# Accelerometer_Schematic_Rev1.net
KiCad netlist of a schematic drawn in EAGLE
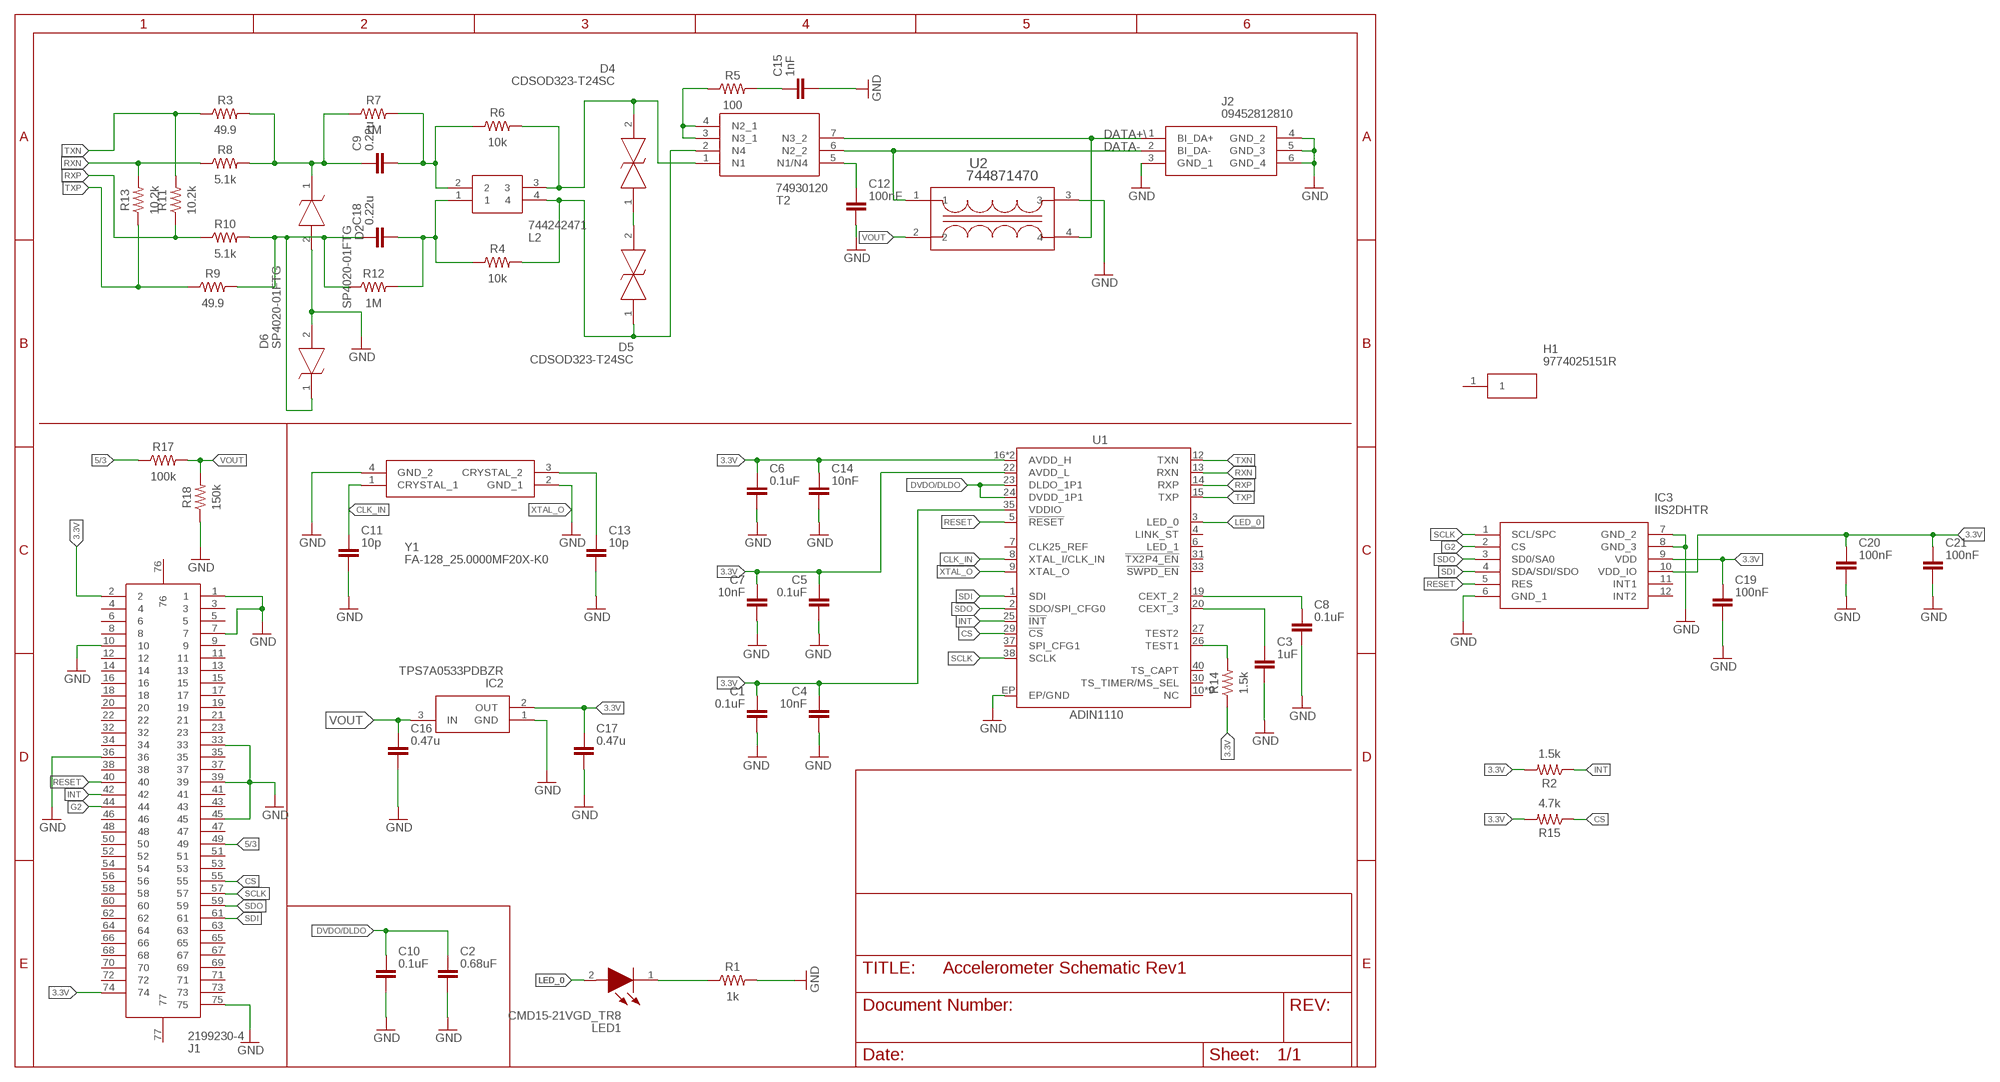
[diagram p0: schematic, sheet 1]

(export (version "E")
  (design (tool "Eeschema 10.0.6"))
  (components
    (comp (ref "C1")
      (value "0.1uF")
      (footprint "eagle-import:CAPC1005X60")
      (libsource (lib "eagle-import") (part "CCHIP-0402(1005-METRIC)_"))
    )
    (comp (ref "C2")
      (value "0.68uF")
      (footprint "eagle-import:CAPC1005X60")
      (libsource (lib "eagle-import") (part "CCHIP-0402(1005-METRIC)_"))
    )
    (comp (ref "C3")
      (value "1uF")
      (footprint "eagle-import:CAPC1005X60")
      (libsource (lib "eagle-import") (part "CCHIP-0402(1005-METRIC)_"))
    )
    (comp (ref "C4")
      (value "10nF")
      (footprint "eagle-import:CAPC1005X60")
      (libsource (lib "eagle-import") (part "CCHIP-0402(1005-METRIC)_"))
    )
    (comp (ref "C5")
      (value "0.1uF")
      (footprint "eagle-import:CAPC1005X60")
      (libsource (lib "eagle-import") (part "CCHIP-0402(1005-METRIC)_"))
    )
    (comp (ref "C6")
      (value "0.1uF")
      (footprint "eagle-import:CAPC1005X60")
      (libsource (lib "eagle-import") (part "CCHIP-0402(1005-METRIC)_"))
    )
    (comp (ref "C7")
      (value "10nF")
      (footprint "eagle-import:CAPC1005X60")
      (libsource (lib "eagle-import") (part "CCHIP-0402(1005-METRIC)_"))
    )
    (comp (ref "C8")
      (value "0.1uF")
      (footprint "eagle-import:CAPC1005X60")
      (libsource (lib "eagle-import") (part "CCHIP-0402(1005-METRIC)_"))
    )
    (comp (ref "C9")
      (value "0.22u")
      (footprint "eagle-import:CAPC1005X60")
      (libsource (lib "eagle-import") (part "CCHIP-0402(1005-METRIC)_"))
    )
    (comp (ref "C10")
      (value "0.1uF")
      (footprint "eagle-import:CAPC1005X60")
      (libsource (lib "eagle-import") (part "CCHIP-0402(1005-METRIC)_"))
    )
    (comp (ref "C11")
      (value "10p")
      (footprint "eagle-import:CAPC1005X60")
      (libsource (lib "eagle-import") (part "CCHIP-0402(1005-METRIC)_"))
    )
    (comp (ref "C12")
      (value "100nF")
      (footprint "eagle-import:CAPC1005X60")
      (libsource (lib "eagle-import") (part "CCHIP-0402(1005-METRIC)_"))
    )
    (comp (ref "C13")
      (value "10p")
      (footprint "eagle-import:CAPC1005X60")
      (libsource (lib "eagle-import") (part "CCHIP-0402(1005-METRIC)_"))
    )
    (comp (ref "C14")
      (value "10nF")
      (footprint "eagle-import:CAPC1005X60")
      (libsource (lib "eagle-import") (part "CCHIP-0402(1005-METRIC)_"))
    )
    (comp (ref "C15")
      (value "1nF")
      (footprint "eagle-import:CAPC1005X60")
      (libsource (lib "eagle-import") (part "CCHIP-0402(1005-METRIC)_"))
    )
    (comp (ref "C16")
      (value "0.47u")
      (footprint "eagle-import:CAPC1005X60")
      (libsource (lib "eagle-import") (part "CCHIP-0402(1005-METRIC)_"))
    )
    (comp (ref "C17")
      (value "0.47u")
      (footprint "eagle-import:CAPC1005X60")
      (libsource (lib "eagle-import") (part "CCHIP-0402(1005-METRIC)_"))
    )
    (comp (ref "C18")
      (value "0.22u")
      (footprint "eagle-import:CAPC1005X60")
      (libsource (lib "eagle-import") (part "CCHIP-0402(1005-METRIC)_"))
    )
    (comp (ref "C19")
      (value "100nF")
      (footprint "eagle-import:CAPC1005X60")
      (libsource (lib "eagle-import") (part "CCHIP-0402(1005-METRIC)_"))
    )
    (comp (ref "C20")
      (value "100nF")
      (footprint "eagle-import:CAPC1005X60")
      (libsource (lib "eagle-import") (part "CCHIP-0402(1005-METRIC)_"))
    )
    (comp (ref "C21")
      (value "100nF")
      (footprint "eagle-import:CAPC1005X60")
      (libsource (lib "eagle-import") (part "CCHIP-0402(1005-METRIC)_"))
    )
    (comp (ref "D2")
      (value "SP4020-01FTG")
      (footprint "eagle-import:SOD2613X114N")
      (fields (field (name "MOUSER_PART_NUMBER") "576-SP4020-01FTG"))
      (libsource (lib "eagle-import") (part "SP4020-01FTG"))
    )
    (comp (ref "D4")
      (value "CDSOD323-T24SC")
      (footprint "eagle-import:SOD2513X114N")
      (fields (field (name "MOUSER_PART_NUMBER") "652-CDSOD323-T24SC"))
      (libsource (lib "eagle-import") (part "CDSOD323-T24SC"))
    )
    (comp (ref "D5")
      (value "CDSOD323-T24SC")
      (footprint "eagle-import:SOD2513X114N")
      (fields (field (name "MOUSER_PART_NUMBER") "652-CDSOD323-T24SC"))
      (libsource (lib "eagle-import") (part "CDSOD323-T24SC"))
    )
    (comp (ref "D6")
      (value "SP4020-01FTG")
      (footprint "eagle-import:SOD2613X114N")
      (fields (field (name "MOUSER_PART_NUMBER") "576-SP4020-01FTG"))
      (libsource (lib "eagle-import") (part "SP4020-01FTG"))
    )
    (comp (ref "H1")
      (value "9774025151R")
      (footprint "eagle-import:9774025151R")
      (fields (field (name "MOUSER_PART_NUMBER") "710-9774025151R"))
      (libsource (lib "eagle-import") (part "9774025151R"))
    )
    (comp (ref "IC2")
      (value "TPS7A0533PDBZR")
      (footprint "eagle-import:SOT95P237X112-3N")
      (fields (field (name "MOUSER_PART_NUMBER") "595-TPS7A0533PDBZR"))
      (libsource (lib "eagle-import") (part "TPS7A0533PDBZR"))
    )
    (comp (ref "IC3")
      (value "IIS2DHTR")
      (footprint "eagle-import:LGA-12")
      (fields (field (name "MOUSER_PART_NUMBER") "511-IIS2DHTR"))
      (libsource (lib "eagle-import") (part "IIS2DHTR"))
    )
    (comp (ref "J1")
      (value "2199230-4")
      (footprint "eagle-import:21992304")
      (fields (field (name "MOUSER_PART_NUMBER") "571-2199230-4"))
      (libsource (lib "eagle-import") (part "2199230-4"))
    )
    (comp (ref "J2")
      (value "09452812810")
      (footprint "eagle-import:09452812810")
      (fields (field (name "MOUSER_PART_NUMBER") "617-09452812810"))
      (libsource (lib "eagle-import") (part "09452812810"))
    )
    (comp (ref "L2")
      (value "744242471")
      (footprint "eagle-import:744242471")
      (fields (field (name "MOUSER_PART_NUMBER") "710-744242471"))
      (libsource (lib "eagle-import") (part "744242471"))
    )
    (comp (ref "LED1")
      (value "CMD15-21VGD_TR8")
      (footprint "eagle-import:LEDC3215X130N")
      (fields
        (field (name "ARROW_PART_NUMBER") "CMD15-21VGD/TR8")
        (field (name "MOUSER_PART_NUMBER") "606-CMD15-21VGD/TR8")
      )
      (libsource (lib "eagle-import") (part "CMD15-21VGD_TR8"))
    )
    (comp (ref "R1")
      (value "1k")
      (footprint "eagle-import:RESC1005X40")
      (libsource (lib "eagle-import") (part "R-USCHIP-0402(1005-METRIC)_"))
    )
    (comp (ref "R2")
      (value "1.5k")
      (footprint "eagle-import:RESC1005X40")
      (libsource (lib "eagle-import") (part "R-USCHIP-0402(1005-METRIC)_"))
    )
    (comp (ref "R3")
      (value "49.9")
      (footprint "eagle-import:RESC1005X40")
      (libsource (lib "eagle-import") (part "R-USCHIP-0402(1005-METRIC)_"))
    )
    (comp (ref "R4")
      (value "10k")
      (footprint "eagle-import:RESC1005X40")
      (libsource (lib "eagle-import") (part "R-USCHIP-0402(1005-METRIC)_"))
    )
    (comp (ref "R5")
      (value "100")
      (footprint "eagle-import:RESC1005X40")
      (libsource (lib "eagle-import") (part "R-USCHIP-0402(1005-METRIC)_"))
    )
    (comp (ref "R6")
      (value "10k")
      (footprint "eagle-import:RESC1005X40")
      (libsource (lib "eagle-import") (part "R-USCHIP-0402(1005-METRIC)_"))
    )
    (comp (ref "R7")
      (value "1M")
      (footprint "eagle-import:RESC1005X40")
      (libsource (lib "eagle-import") (part "R-USCHIP-0402(1005-METRIC)_"))
    )
    (comp (ref "R8")
      (value "5.1k")
      (footprint "eagle-import:RESC1005X40")
      (libsource (lib "eagle-import") (part "R-USCHIP-0402(1005-METRIC)_"))
    )
    (comp (ref "R9")
      (value "49.9")
      (footprint "eagle-import:RESC1005X40")
      (libsource (lib "eagle-import") (part "R-USCHIP-0402(1005-METRIC)_"))
    )
    (comp (ref "R10")
      (value "5.1k")
      (footprint "eagle-import:RESC1005X40")
      (libsource (lib "eagle-import") (part "R-USCHIP-0402(1005-METRIC)_"))
    )
    (comp (ref "R11")
      (value "10.2k")
      (footprint "eagle-import:RESC1005X40")
      (libsource (lib "eagle-import") (part "R-USCHIP-0402(1005-METRIC)_"))
    )
    (comp (ref "R12")
      (value "1M")
      (footprint "eagle-import:RESC1005X40")
      (libsource (lib "eagle-import") (part "R-USCHIP-0402(1005-METRIC)_"))
    )
    (comp (ref "R13")
      (value "10.2k")
      (footprint "eagle-import:RESC1005X40")
      (libsource (lib "eagle-import") (part "R-USCHIP-0402(1005-METRIC)_"))
    )
    (comp (ref "R14")
      (value "1.5k")
      (footprint "eagle-import:RESC1005X40")
      (libsource (lib "eagle-import") (part "R-USCHIP-0402(1005-METRIC)_"))
    )
    (comp (ref "R15")
      (value "4.7k")
      (footprint "eagle-import:RESC1005X40")
      (libsource (lib "eagle-import") (part "R-USCHIP-0402(1005-METRIC)_"))
    )
    (comp (ref "R17")
      (value "100k")
      (footprint "eagle-import:RESC1005X40")
      (libsource (lib "eagle-import") (part "R-USCHIP-0402(1005-METRIC)_"))
    )
    (comp (ref "R18")
      (value "150k")
      (footprint "eagle-import:RESC1005X40")
      (libsource (lib "eagle-import") (part "R-USCHIP-0402(1005-METRIC)_"))
    )
    (comp (ref "T2")
      (value "74930120")
      (footprint "eagle-import:74930120")
      (fields (field (name "MOUSER_PART_NUMBER") "710-74930120"))
      (libsource (lib "eagle-import") (part "74930120"))
    )
    (comp (ref "U1")
      (value "ADIN1110")
      (footprint "eagle-import:LFCSP-40")
      (libsource (lib "eagle-import") (part "ADIN1110"))
    )
    (comp (ref "U2")
      (value "744871470")
      (footprint "eagle-import:SMT_871470_WRE")
      (fields (field (name "COPYRIGHT") "Copyright (C) 2023 Ultra Librarian. All rights reserved."))
      (libsource (lib "eagle-import") (part "744871470"))
    )
    (comp (ref "Y1")
      (value "FA-128_25.0000MF20X-K0")
      (footprint "eagle-import:FA128250000MF20XK0")
      (fields
        (field (name "MANUFACTURER_PART_NUMBER") "FA-128 25.0000MF20X-K0")
        (field (name "MOUSER_PART_NUMBER") "732-FA-12825F20X-K0")
      )
      (libsource (lib "eagle-import") (part "FA-128_25.0000MF20X-K0"))
    )
  )
  (nets
    (net (code "1") (name "/DATA+\\") (class "Default")
      (node (ref "J2") (pin "1") (pinfunction "BI_DA+_1") (pintype "bidirectional"))
      (node (ref "T2") (pin "7") (pinfunction "N3_2_7") (pintype "bidirectional"))
      (node (ref "U2") (pin "4") (pinfunction "4_4") (pintype "passive"))
    )
    (net (code "2") (name "/DATA-") (class "Default")
      (node (ref "J2") (pin "2") (pinfunction "BI_DA-_2") (pintype "bidirectional"))
      (node (ref "T2") (pin "6") (pinfunction "N2_2_6") (pintype "bidirectional"))
      (node (ref "U2") (pin "1") (pinfunction "1_1") (pintype "passive"))
    )
    (net (code "3") (name "3.3V") (class "Default")
      (node (ref "C1") (pin "1") (pinfunction "1_1") (pintype "passive"))
      (node (ref "C14") (pin "1") (pinfunction "1_1") (pintype "passive"))
      (node (ref "C17") (pin "1") (pinfunction "1_1") (pintype "passive"))
      (node (ref "C19") (pin "1") (pinfunction "1_1") (pintype "passive"))
      (node (ref "C20") (pin "1") (pinfunction "1_1") (pintype "passive"))
      (node (ref "C21") (pin "1") (pinfunction "1_1") (pintype "passive"))
      (node (ref "C4") (pin "1") (pinfunction "1_1") (pintype "passive"))
      (node (ref "C5") (pin "1") (pinfunction "1_1") (pintype "passive"))
      (node (ref "C6") (pin "1") (pinfunction "1_1") (pintype "passive"))
      (node (ref "C7") (pin "1") (pinfunction "1_1") (pintype "passive"))
      (node (ref "IC2") (pin "2") (pinfunction "OUT_2") (pintype "output"))
      (node (ref "IC3") (pin "10") (pinfunction "VDD_IO_10") (pintype "bidirectional"))
      (node (ref "IC3") (pin "9") (pinfunction "VDD_9") (pintype "bidirectional"))
      (node (ref "J1") (pin "2") (pinfunction "2_2") (pintype "bidirectional"))
      (node (ref "J1") (pin "74") (pinfunction "74_74") (pintype "bidirectional"))
      (node (ref "R14") (pin "1") (pinfunction "1_1") (pintype "passive"))
      (node (ref "R15") (pin "2") (pinfunction "2_2") (pintype "passive"))
      (node (ref "R2") (pin "2") (pinfunction "2_2") (pintype "passive"))
      (node (ref "U1") (pin "16") (pinfunction "AVDD_H_16") (pintype "bidirectional"))
      (node (ref "U1") (pin "17") (pinfunction "AVDD_H_17") (pintype "bidirectional"))
      (node (ref "U1") (pin "22") (pinfunction "AVDD_L_22") (pintype "bidirectional"))
      (node (ref "U1") (pin "35") (pinfunction "VDDIO_35") (pintype "bidirectional"))
    )
    (net (code "4") (name "5{slash}3") (class "Default")
      (node (ref "J1") (pin "49") (pinfunction "49_49") (pintype "bidirectional"))
      (node (ref "R17") (pin "1") (pinfunction "1_1") (pintype "passive"))
    )
    (net (code "5") (name "CLK_IN") (class "Default")
      (node (ref "C11") (pin "1") (pinfunction "1_1") (pintype "passive"))
      (node (ref "U1") (pin "8") (pinfunction "XTAL_I/CLK_IN_8") (pintype "bidirectional"))
      (node (ref "Y1") (pin "1") (pinfunction "CRYSTAL_1_1") (pintype "bidirectional"))
    )
    (net (code "6") (name "CS") (class "Default")
      (node (ref "J1") (pin "55") (pinfunction "55_55") (pintype "bidirectional"))
      (node (ref "R15") (pin "1") (pinfunction "1_1") (pintype "passive"))
      (node (ref "U1") (pin "29") (pinfunction "~{CS}_29") (pintype "bidirectional"))
    )
    (net (code "7") (name "DVDO{slash}DLDO") (class "Default")
      (node (ref "C10") (pin "1") (pinfunction "1_1") (pintype "passive"))
      (node (ref "C2") (pin "1") (pinfunction "1_1") (pintype "passive"))
      (node (ref "U1") (pin "23") (pinfunction "DLDO_1P1_23") (pintype "bidirectional"))
      (node (ref "U1") (pin "24") (pinfunction "DVDD_1P1_24") (pintype "bidirectional"))
    )
    (net (code "8") (name "G2") (class "Default")
      (node (ref "IC3") (pin "2") (pinfunction "CS_2") (pintype "bidirectional"))
      (node (ref "J1") (pin "44") (pinfunction "44_44") (pintype "bidirectional"))
    )
    (net (code "9") (name "GND") (class "Default")
      (node (ref "C1") (pin "2") (pinfunction "2_2") (pintype "passive"))
      (node (ref "C10") (pin "2") (pinfunction "2_2") (pintype "passive"))
      (node (ref "C11") (pin "2") (pinfunction "2_2") (pintype "passive"))
      (node (ref "C12") (pin "2") (pinfunction "2_2") (pintype "passive"))
      (node (ref "C13") (pin "2") (pinfunction "2_2") (pintype "passive"))
      (node (ref "C14") (pin "2") (pinfunction "2_2") (pintype "passive"))
      (node (ref "C15") (pin "2") (pinfunction "2_2") (pintype "passive"))
      (node (ref "C16") (pin "2") (pinfunction "2_2") (pintype "passive"))
      (node (ref "C17") (pin "2") (pinfunction "2_2") (pintype "passive"))
      (node (ref "C19") (pin "2") (pinfunction "2_2") (pintype "passive"))
      (node (ref "C2") (pin "2") (pinfunction "2_2") (pintype "passive"))
      (node (ref "C20") (pin "2") (pinfunction "2_2") (pintype "passive"))
      (node (ref "C21") (pin "2") (pinfunction "2_2") (pintype "passive"))
      (node (ref "C3") (pin "2") (pinfunction "2_2") (pintype "passive"))
      (node (ref "C4") (pin "2") (pinfunction "2_2") (pintype "passive"))
      (node (ref "C5") (pin "2") (pinfunction "2_2") (pintype "passive"))
      (node (ref "C6") (pin "2") (pinfunction "2_2") (pintype "passive"))
      (node (ref "C7") (pin "2") (pinfunction "2_2") (pintype "passive"))
      (node (ref "C8") (pin "2") (pinfunction "2_2") (pintype "passive"))
      (node (ref "D2") (pin "2") (pinfunction "A_2") (pintype "bidirectional"))
      (node (ref "D6") (pin "2") (pinfunction "A_2") (pintype "bidirectional"))
      (node (ref "IC2") (pin "1") (pinfunction "GND_1") (pintype "power_in"))
      (node (ref "IC3") (pin "6") (pinfunction "GND_1_6") (pintype "bidirectional"))
      (node (ref "IC3") (pin "7") (pinfunction "GND_2_7") (pintype "bidirectional"))
      (node (ref "IC3") (pin "8") (pinfunction "GND_3_8") (pintype "bidirectional"))
      (node (ref "J1") (pin "1") (pinfunction "1_1") (pintype "bidirectional"))
      (node (ref "J1") (pin "10") (pinfunction "10_10") (pintype "bidirectional"))
      (node (ref "J1") (pin "33") (pinfunction "33_33") (pintype "bidirectional"))
      (node (ref "J1") (pin "36") (pinfunction "36_36") (pintype "bidirectional"))
      (node (ref "J1") (pin "39") (pinfunction "39_39") (pintype "bidirectional"))
      (node (ref "J1") (pin "45") (pinfunction "45_45") (pintype "bidirectional"))
      (node (ref "J1") (pin "7") (pinfunction "7_7") (pintype "bidirectional"))
      (node (ref "J1") (pin "75") (pinfunction "75_75") (pintype "bidirectional"))
      (node (ref "J2") (pin "3") (pinfunction "GND_1_3") (pintype "bidirectional"))
      (node (ref "J2") (pin "4") (pinfunction "GND_2_4") (pintype "bidirectional"))
      (node (ref "J2") (pin "5") (pinfunction "GND_3_5") (pintype "bidirectional"))
      (node (ref "J2") (pin "6") (pinfunction "GND_4_6") (pintype "bidirectional"))
      (node (ref "R1") (pin "2") (pinfunction "2_2") (pintype "passive"))
      (node (ref "R18") (pin "1") (pinfunction "1_1") (pintype "passive"))
      (node (ref "U1") (pin "EP") (pinfunction "EP/GND_EP") (pintype "bidirectional"))
      (node (ref "U2") (pin "3") (pinfunction "3_3") (pintype "passive"))
      (node (ref "Y1") (pin "2") (pinfunction "GND_1_2") (pintype "bidirectional"))
      (node (ref "Y1") (pin "4") (pinfunction "GND_2_4") (pintype "bidirectional"))
    )
    (net (code "10") (name "INT") (class "Default")
      (node (ref "J1") (pin "42") (pinfunction "42_42") (pintype "bidirectional"))
      (node (ref "R2") (pin "1") (pinfunction "1_1") (pintype "passive"))
      (node (ref "U1") (pin "25") (pinfunction "~{INT}_25") (pintype "bidirectional"))
    )
    (net (code "11") (name "LED_0") (class "Default")
      (node (ref "LED1") (pin "2") (pinfunction "A_2") (pintype "bidirectional"))
      (node (ref "U1") (pin "3") (pinfunction "LED_0_3") (pintype "bidirectional"))
    )
    (net (code "12") (name "Net-(C9-Pad2)") (class "Default")
      (node (ref "C9") (pin "2") (pinfunction "2_2") (pintype "passive"))
      (node (ref "L2") (pin "2") (pinfunction "2_2") (pintype "bidirectional"))
      (node (ref "R6") (pin "1") (pinfunction "1_1") (pintype "passive"))
      (node (ref "R7") (pin "2") (pinfunction "2_2") (pintype "passive"))
    )
    (net (code "13") (name "Net-(C15-Pad1)") (class "Default")
      (node (ref "C15") (pin "1") (pinfunction "1_1") (pintype "passive"))
      (node (ref "R5") (pin "2") (pinfunction "2_2") (pintype "passive"))
    )
    (net (code "14") (name "Net-(C18-Pad2)") (class "Default")
      (node (ref "C18") (pin "2") (pinfunction "2_2") (pintype "passive"))
      (node (ref "L2") (pin "1") (pinfunction "1_1") (pintype "bidirectional"))
      (node (ref "R12") (pin "2") (pinfunction "2_2") (pintype "passive"))
      (node (ref "R4") (pin "1") (pinfunction "1_1") (pintype "passive"))
    )
    (net (code "15") (name "Net-(D2-K)") (class "Default")
      (node (ref "C9") (pin "1") (pinfunction "1_1") (pintype "passive"))
      (node (ref "D2") (pin "1") (pinfunction "K_1") (pintype "bidirectional"))
      (node (ref "R3") (pin "2") (pinfunction "2_2") (pintype "passive"))
      (node (ref "R7") (pin "1") (pinfunction "1_1") (pintype "passive"))
      (node (ref "R8") (pin "2") (pinfunction "2_2") (pintype "passive"))
    )
    (net (code "16") (name "Net-(D4-Pad1)") (class "Default")
      (node (ref "D4") (pin "1") (pinfunction "1_1") (pintype "bidirectional"))
      (node (ref "D5") (pin "2") (pinfunction "2_2") (pintype "bidirectional"))
    )
    (net (code "17") (name "Net-(D6-K)") (class "Default")
      (node (ref "C18") (pin "1") (pinfunction "1_1") (pintype "passive"))
      (node (ref "D6") (pin "1") (pinfunction "K_1") (pintype "bidirectional"))
      (node (ref "R10") (pin "2") (pinfunction "2_2") (pintype "passive"))
      (node (ref "R12") (pin "1") (pinfunction "1_1") (pintype "passive"))
      (node (ref "R9") (pin "2") (pinfunction "2_2") (pintype "passive"))
    )
    (net (code "18") (name "Net-(LED1-K)") (class "Default")
      (node (ref "LED1") (pin "1") (pinfunction "K_1") (pintype "bidirectional"))
      (node (ref "R1") (pin "1") (pinfunction "1_1") (pintype "passive"))
    )
    (net (code "19") (name "Net-(T2-N1)") (class "Default")
      (node (ref "D4") (pin "2") (pinfunction "2_2") (pintype "bidirectional"))
      (node (ref "L2") (pin "3") (pinfunction "3_3") (pintype "bidirectional"))
      (node (ref "R6") (pin "2") (pinfunction "2_2") (pintype "passive"))
      (node (ref "T2") (pin "1") (pinfunction "N1_1") (pintype "bidirectional"))
    )
    (net (code "20") (name "Net-(T2-N1{slash}N4)") (class "Default")
      (node (ref "C12") (pin "1") (pinfunction "1_1") (pintype "passive"))
      (node (ref "T2") (pin "5") (pinfunction "N1/N4_5") (pintype "bidirectional"))
    )
    (net (code "21") (name "Net-(T2-N2_1)") (class "Default")
      (node (ref "R5") (pin "1") (pinfunction "1_1") (pintype "passive"))
      (node (ref "T2") (pin "3") (pinfunction "N3_1_3") (pintype "bidirectional"))
      (node (ref "T2") (pin "4") (pinfunction "N2_1_4") (pintype "bidirectional"))
    )
    (net (code "22") (name "Net-(T2-N4)") (class "Default")
      (node (ref "D5") (pin "1") (pinfunction "1_1") (pintype "bidirectional"))
      (node (ref "L2") (pin "4") (pinfunction "4_4") (pintype "bidirectional"))
      (node (ref "R4") (pin "2") (pinfunction "2_2") (pintype "passive"))
      (node (ref "T2") (pin "2") (pinfunction "N4_2") (pintype "bidirectional"))
    )
    (net (code "23") (name "Net-(U1-CEXT_2)") (class "Default")
      (node (ref "C8") (pin "1") (pinfunction "1_1") (pintype "passive"))
      (node (ref "U1") (pin "19") (pinfunction "CEXT_2_19") (pintype "bidirectional"))
    )
    (net (code "24") (name "Net-(U1-CEXT_3)") (class "Default")
      (node (ref "C3") (pin "1") (pinfunction "1_1") (pintype "passive"))
      (node (ref "U1") (pin "20") (pinfunction "CEXT_3_20") (pintype "bidirectional"))
    )
    (net (code "25") (name "Net-(U1-TEST1)") (class "Default")
      (node (ref "R14") (pin "2") (pinfunction "2_2") (pintype "passive"))
      (node (ref "U1") (pin "26") (pinfunction "TEST1_26") (pintype "bidirectional"))
    )
    (net (code "26") (name "RESET") (class "Default")
      (node (ref "IC3") (pin "5") (pinfunction "RES_5") (pintype "bidirectional"))
      (node (ref "J1") (pin "40") (pinfunction "40_40") (pintype "bidirectional"))
      (node (ref "U1") (pin "5") (pinfunction "~{RESET}_5") (pintype "bidirectional"))
    )
    (net (code "27") (name "RXN") (class "Default")
      (node (ref "R13") (pin "2") (pinfunction "2_2") (pintype "passive"))
      (node (ref "R8") (pin "1") (pinfunction "1_1") (pintype "passive"))
      (node (ref "U1") (pin "13") (pinfunction "RXN_13") (pintype "bidirectional"))
    )
    (net (code "28") (name "RXP") (class "Default")
      (node (ref "R10") (pin "1") (pinfunction "1_1") (pintype "passive"))
      (node (ref "R11") (pin "1") (pinfunction "1_1") (pintype "passive"))
      (node (ref "U1") (pin "14") (pinfunction "RXP_14") (pintype "bidirectional"))
    )
    (net (code "29") (name "SCLK") (class "Default")
      (node (ref "IC3") (pin "1") (pinfunction "SCL/SPC_1") (pintype "bidirectional"))
      (node (ref "J1") (pin "57") (pinfunction "57_57") (pintype "bidirectional"))
      (node (ref "U1") (pin "38") (pinfunction "SCLK_38") (pintype "bidirectional"))
    )
    (net (code "30") (name "SDI") (class "Default")
      (node (ref "IC3") (pin "4") (pinfunction "SDA/SDI/SDO_4") (pintype "bidirectional"))
      (node (ref "J1") (pin "61") (pinfunction "61_61") (pintype "bidirectional"))
      (node (ref "U1") (pin "1") (pinfunction "SDI_1") (pintype "bidirectional"))
    )
    (net (code "31") (name "SDO") (class "Default")
      (node (ref "IC3") (pin "3") (pinfunction "SD0/SA0_3") (pintype "bidirectional"))
      (node (ref "J1") (pin "59") (pinfunction "59_59") (pintype "bidirectional"))
      (node (ref "U1") (pin "2") (pinfunction "SDO/SPI_CFG0_2") (pintype "bidirectional"))
    )
    (net (code "32") (name "TXN") (class "Default")
      (node (ref "R11") (pin "2") (pinfunction "2_2") (pintype "passive"))
      (node (ref "R3") (pin "1") (pinfunction "1_1") (pintype "passive"))
      (node (ref "U1") (pin "12") (pinfunction "TXN_12") (pintype "bidirectional"))
    )
    (net (code "33") (name "TXP") (class "Default")
      (node (ref "R13") (pin "1") (pinfunction "1_1") (pintype "passive"))
      (node (ref "R9") (pin "1") (pinfunction "1_1") (pintype "passive"))
      (node (ref "U1") (pin "15") (pinfunction "TXP_15") (pintype "bidirectional"))
    )
    (net (code "34") (name "VOUT") (class "Default")
      (node (ref "C16") (pin "1") (pinfunction "1_1") (pintype "passive"))
      (node (ref "IC2") (pin "3") (pinfunction "IN_3") (pintype "input"))
      (node (ref "R17") (pin "2") (pinfunction "2_2") (pintype "passive"))
      (node (ref "R18") (pin "2") (pinfunction "2_2") (pintype "passive"))
      (node (ref "U2") (pin "2") (pinfunction "2_2") (pintype "passive"))
    )
    (net (code "35") (name "XTAL_O") (class "Default")
      (node (ref "C13") (pin "1") (pinfunction "1_1") (pintype "passive"))
      (node (ref "U1") (pin "9") (pinfunction "XTAL_O_9") (pintype "bidirectional"))
      (node (ref "Y1") (pin "3") (pinfunction "CRYSTAL_2_3") (pintype "bidirectional"))
    )
    (net (code "36") (name "unconnected-(H1-Pad1)") (class "Default")
      (node (ref "H1") (pin "1") (pinfunction "1_1") (pintype "bidirectional"))
    )
    (net (code "37") (name "unconnected-(IC3-INT1-Pad11)") (class "Default")
      (node (ref "IC3") (pin "11") (pinfunction "INT1_11") (pintype "bidirectional"))
    )
    (net (code "38") (name "unconnected-(IC3-INT2-Pad12)") (class "Default")
      (node (ref "IC3") (pin "12") (pinfunction "INT2_12") (pintype "bidirectional"))
    )
    (net (code "39") (name "unconnected-(J1-Pad3)") (class "Default")
      (node (ref "J1") (pin "3") (pinfunction "3_3") (pintype "bidirectional"))
    )
    (net (code "40") (name "unconnected-(J1-Pad4)") (class "Default")
      (node (ref "J1") (pin "4") (pinfunction "4_4") (pintype "bidirectional"))
    )
    (net (code "41") (name "unconnected-(J1-Pad5)") (class "Default")
      (node (ref "J1") (pin "5") (pinfunction "5_5") (pintype "bidirectional"))
    )
    (net (code "42") (name "unconnected-(J1-Pad6)") (class "Default")
      (node (ref "J1") (pin "6") (pinfunction "6_6") (pintype "bidirectional"))
    )
    (net (code "43") (name "unconnected-(J1-Pad8)") (class "Default")
      (node (ref "J1") (pin "8") (pinfunction "8_8") (pintype "bidirectional"))
    )
    (net (code "44") (name "unconnected-(J1-Pad9)") (class "Default")
      (node (ref "J1") (pin "9") (pinfunction "9_9") (pintype "bidirectional"))
    )
    (net (code "45") (name "unconnected-(J1-Pad11)") (class "Default")
      (node (ref "J1") (pin "11") (pinfunction "11_11") (pintype "bidirectional"))
    )
    (net (code "46") (name "unconnected-(J1-Pad12)") (class "Default")
      (node (ref "J1") (pin "12") (pinfunction "12_12") (pintype "bidirectional"))
    )
    (net (code "47") (name "unconnected-(J1-Pad13)") (class "Default")
      (node (ref "J1") (pin "13") (pinfunction "13_13") (pintype "bidirectional"))
    )
    (net (code "48") (name "unconnected-(J1-Pad14)") (class "Default")
      (node (ref "J1") (pin "14") (pinfunction "14_14") (pintype "bidirectional"))
    )
    (net (code "49") (name "unconnected-(J1-Pad15)") (class "Default")
      (node (ref "J1") (pin "15") (pinfunction "15_15") (pintype "bidirectional"))
    )
    (net (code "50") (name "unconnected-(J1-Pad16)") (class "Default")
      (node (ref "J1") (pin "16") (pinfunction "16_16") (pintype "bidirectional"))
    )
    (net (code "51") (name "unconnected-(J1-Pad17)") (class "Default")
      (node (ref "J1") (pin "17") (pinfunction "17_17") (pintype "bidirectional"))
    )
    (net (code "52") (name "unconnected-(J1-Pad18)") (class "Default")
      (node (ref "J1") (pin "18") (pinfunction "18_18") (pintype "bidirectional"))
    )
    (net (code "53") (name "unconnected-(J1-Pad19)") (class "Default")
      (node (ref "J1") (pin "19") (pinfunction "19_19") (pintype "bidirectional"))
    )
    (net (code "54") (name "unconnected-(J1-Pad20)") (class "Default")
      (node (ref "J1") (pin "20") (pinfunction "20_20") (pintype "bidirectional"))
    )
    (net (code "55") (name "unconnected-(J1-Pad21)") (class "Default")
      (node (ref "J1") (pin "21") (pinfunction "21_21") (pintype "bidirectional"))
    )
    (net (code "56") (name "unconnected-(J1-Pad22)") (class "Default")
      (node (ref "J1") (pin "22") (pinfunction "22_22") (pintype "bidirectional"))
    )
    (net (code "57") (name "unconnected-(J1-Pad23)") (class "Default")
      (node (ref "J1") (pin "23") (pinfunction "23_23") (pintype "bidirectional"))
    )
    (net (code "58") (name "unconnected-(J1-Pad32)") (class "Default")
      (node (ref "J1") (pin "32") (pinfunction "32_32") (pintype "bidirectional"))
    )
    (net (code "59") (name "unconnected-(J1-Pad34)") (class "Default")
      (node (ref "J1") (pin "34") (pinfunction "34_34") (pintype "bidirectional"))
    )
    (net (code "60") (name "unconnected-(J1-Pad35)") (class "Default")
      (node (ref "J1") (pin "35") (pinfunction "35_35") (pintype "bidirectional"))
    )
    (net (code "61") (name "unconnected-(J1-Pad37)") (class "Default")
      (node (ref "J1") (pin "37") (pinfunction "37_37") (pintype "bidirectional"))
    )
    (net (code "62") (name "unconnected-(J1-Pad38)") (class "Default")
      (node (ref "J1") (pin "38") (pinfunction "38_38") (pintype "bidirectional"))
    )
    (net (code "63") (name "unconnected-(J1-Pad41)") (class "Default")
      (node (ref "J1") (pin "41") (pinfunction "41_41") (pintype "bidirectional"))
    )
    (net (code "64") (name "unconnected-(J1-Pad43)") (class "Default")
      (node (ref "J1") (pin "43") (pinfunction "43_43") (pintype "bidirectional"))
    )
    (net (code "65") (name "unconnected-(J1-Pad46)") (class "Default")
      (node (ref "J1") (pin "46") (pinfunction "46_46") (pintype "bidirectional"))
    )
    (net (code "66") (name "unconnected-(J1-Pad47)") (class "Default")
      (node (ref "J1") (pin "47") (pinfunction "47_47") (pintype "bidirectional"))
    )
    (net (code "67") (name "unconnected-(J1-Pad48)") (class "Default")
      (node (ref "J1") (pin "48") (pinfunction "48_48") (pintype "bidirectional"))
    )
    (net (code "68") (name "unconnected-(J1-Pad50)") (class "Default")
      (node (ref "J1") (pin "50") (pinfunction "50_50") (pintype "bidirectional"))
    )
    (net (code "69") (name "unconnected-(J1-Pad51)") (class "Default")
      (node (ref "J1") (pin "51") (pinfunction "51_51") (pintype "bidirectional"))
    )
    (net (code "70") (name "unconnected-(J1-Pad52)") (class "Default")
      (node (ref "J1") (pin "52") (pinfunction "52_52") (pintype "bidirectional"))
    )
    (net (code "71") (name "unconnected-(J1-Pad53)") (class "Default")
      (node (ref "J1") (pin "53") (pinfunction "53_53") (pintype "bidirectional"))
    )
    (net (code "72") (name "unconnected-(J1-Pad54)") (class "Default")
      (node (ref "J1") (pin "54") (pinfunction "54_54") (pintype "bidirectional"))
    )
    (net (code "73") (name "unconnected-(J1-Pad56)") (class "Default")
      (node (ref "J1") (pin "56") (pinfunction "56_56") (pintype "bidirectional"))
    )
    (net (code "74") (name "unconnected-(J1-Pad58)") (class "Default")
      (node (ref "J1") (pin "58") (pinfunction "58_58") (pintype "bidirectional"))
    )
    (net (code "75") (name "unconnected-(J1-Pad60)") (class "Default")
      (node (ref "J1") (pin "60") (pinfunction "60_60") (pintype "bidirectional"))
    )
    (net (code "76") (name "unconnected-(J1-Pad62)") (class "Default")
      (node (ref "J1") (pin "62") (pinfunction "62_62") (pintype "bidirectional"))
    )
    (net (code "77") (name "unconnected-(J1-Pad63)") (class "Default")
      (node (ref "J1") (pin "63") (pinfunction "63_63") (pintype "bidirectional"))
    )
    (net (code "78") (name "unconnected-(J1-Pad64)") (class "Default")
      (node (ref "J1") (pin "64") (pinfunction "64_64") (pintype "bidirectional"))
    )
    (net (code "79") (name "unconnected-(J1-Pad65)") (class "Default")
      (node (ref "J1") (pin "65") (pinfunction "65_65") (pintype "bidirectional"))
    )
    (net (code "80") (name "unconnected-(J1-Pad66)") (class "Default")
      (node (ref "J1") (pin "66") (pinfunction "66_66") (pintype "bidirectional"))
    )
    (net (code "81") (name "unconnected-(J1-Pad67)") (class "Default")
      (node (ref "J1") (pin "67") (pinfunction "67_67") (pintype "bidirectional"))
    )
    (net (code "82") (name "unconnected-(J1-Pad68)") (class "Default")
      (node (ref "J1") (pin "68") (pinfunction "68_68") (pintype "bidirectional"))
    )
    (net (code "83") (name "unconnected-(J1-Pad69)") (class "Default")
      (node (ref "J1") (pin "69") (pinfunction "69_69") (pintype "bidirectional"))
    )
    (net (code "84") (name "unconnected-(J1-Pad70)") (class "Default")
      (node (ref "J1") (pin "70") (pinfunction "70_70") (pintype "bidirectional"))
    )
    (net (code "85") (name "unconnected-(J1-Pad71)") (class "Default")
      (node (ref "J1") (pin "71") (pinfunction "71_71") (pintype "bidirectional"))
    )
    (net (code "86") (name "unconnected-(J1-Pad72)") (class "Default")
      (node (ref "J1") (pin "72") (pinfunction "72_72") (pintype "bidirectional"))
    )
    (net (code "87") (name "unconnected-(J1-Pad73)") (class "Default")
      (node (ref "J1") (pin "73") (pinfunction "73_73") (pintype "bidirectional"))
    )
    (net (code "88") (name "unconnected-(J1-Pad76)") (class "Default")
      (node (ref "J1") (pin "76") (pinfunction "76_76") (pintype "bidirectional"))
    )
    (net (code "89") (name "unconnected-(J1-Pad77)") (class "Default")
      (node (ref "J1") (pin "77") (pinfunction "77_77") (pintype "bidirectional"))
    )
    (net (code "90") (name "unconnected-(U1-CLK25_REF-Pad7)") (class "Default")
      (node (ref "U1") (pin "7") (pinfunction "CLK25_REF_7") (pintype "bidirectional"))
    )
    (net (code "91") (name "unconnected-(U1-LED_1-Pad6)") (class "Default")
      (node (ref "U1") (pin "6") (pinfunction "LED_1_6") (pintype "bidirectional"))
    )
    (net (code "92") (name "unconnected-(U1-LINK_ST-Pad4)") (class "Default")
      (node (ref "U1") (pin "4") (pinfunction "LINK_ST_4") (pintype "bidirectional"))
    )
    (net (code "93") (name "unconnected-(U1-NC-Pad10)") (class "Default")
      (node (ref "U1") (pin "10") (pinfunction "NC_10") (pintype "no_connect"))
    )
    (net (code "94") (name "unconnected-(U1-NC-Pad11)") (class "Default")
      (node (ref "U1") (pin "11") (pinfunction "NC_11") (pintype "no_connect"))
    )
    (net (code "95") (name "unconnected-(U1-NC-Pad18)") (class "Default")
      (node (ref "U1") (pin "18") (pinfunction "NC_18") (pintype "no_connect"))
    )
    (net (code "96") (name "unconnected-(U1-NC-Pad21)") (class "Default")
      (node (ref "U1") (pin "21") (pinfunction "NC_21") (pintype "no_connect"))
    )
    (net (code "97") (name "unconnected-(U1-NC-Pad28)") (class "Default")
      (node (ref "U1") (pin "28") (pinfunction "NC_28") (pintype "no_connect"))
    )
    (net (code "98") (name "unconnected-(U1-NC-Pad32)") (class "Default")
      (node (ref "U1") (pin "32") (pinfunction "NC_32") (pintype "no_connect"))
    )
    (net (code "99") (name "unconnected-(U1-NC-Pad34)") (class "Default")
      (node (ref "U1") (pin "34") (pinfunction "NC_34") (pintype "no_connect"))
    )
    (net (code "100") (name "unconnected-(U1-NC-Pad36)") (class "Default")
      (node (ref "U1") (pin "36") (pinfunction "NC_36") (pintype "no_connect"))
    )
    (net (code "101") (name "unconnected-(U1-NC-Pad39)") (class "Default")
      (node (ref "U1") (pin "39") (pinfunction "NC_39") (pintype "no_connect"))
    )
    (net (code "102") (name "unconnected-(U1-SPI_CFG1-Pad37)") (class "Default")
      (node (ref "U1") (pin "37") (pinfunction "SPI_CFG1_37") (pintype "bidirectional"))
    )
    (net (code "103") (name "unconnected-(U1-TEST2-Pad27)") (class "Default")
      (node (ref "U1") (pin "27") (pinfunction "TEST2_27") (pintype "bidirectional"))
    )
    (net (code "104") (name "unconnected-(U1-TS_CAPT-Pad40)") (class "Default")
      (node (ref "U1") (pin "40") (pinfunction "TS_CAPT_40") (pintype "bidirectional"))
    )
    (net (code "105") (name "unconnected-(U1-TS_TIMER{slash}MS_SEL-Pad30)") (class "Default")
      (node (ref "U1") (pin "30") (pinfunction "TS_TIMER/MS_SEL_30") (pintype "bidirectional"))
    )
    (net (code "106") (name "unconnected-(U1-~{SWPD_EN}-Pad33)") (class "Default")
      (node (ref "U1") (pin "33") (pinfunction "~{SWPD_EN}_33") (pintype "bidirectional"))
    )
    (net (code "107") (name "unconnected-(U1-~{TX2P4_EN}-Pad31)") (class "Default")
      (node (ref "U1") (pin "31") (pinfunction "~{TX2P4_EN}_31") (pintype "bidirectional"))
    )
  )
)
